# basic_levitator.net
KiCad netlist of a schematic drawn in EAGLE
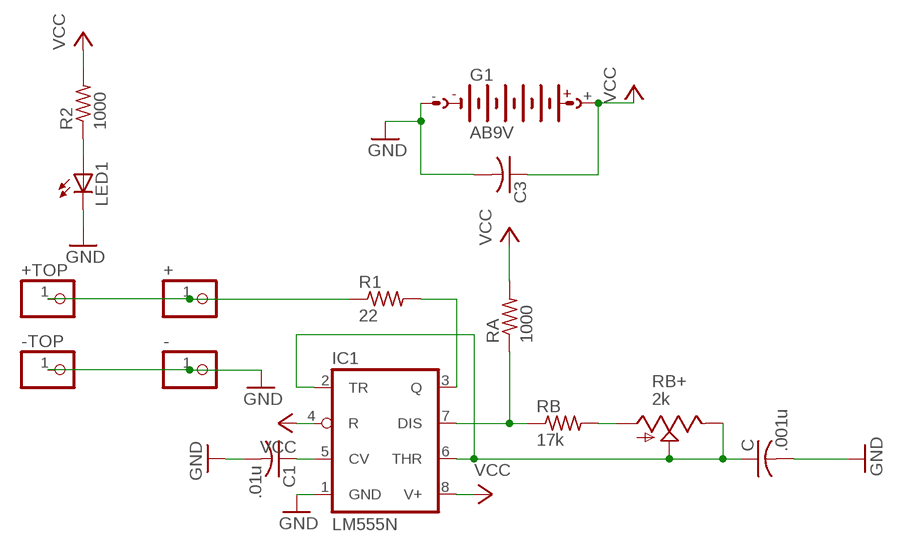
[diagram p0: schematic, sheet 1]

(export (version "E")
  (design (tool "Eeschema 10.0.6"))
  (components
    (comp (ref "+")
      (value "PINHD-1X1")
      (footprint "eagle-import:1X01")
      (libsource (lib "eagle-import") (part "PINHD-1X1"))
    )
    (comp (ref "+TOP")
      (value "PINHD-1X1")
      (footprint "eagle-import:1X01")
      (libsource (lib "eagle-import") (part "PINHD-1X1"))
    )
    (comp (ref "-")
      (value "PINHD-1X1")
      (footprint "eagle-import:1X01")
      (libsource (lib "eagle-import") (part "PINHD-1X1"))
    )
    (comp (ref "-TOP")
      (value "PINHD-1X1")
      (footprint "eagle-import:1X01")
      (libsource (lib "eagle-import") (part "PINHD-1X1"))
    )
    (comp (ref "C")
      (value ".001u")
      (footprint "eagle-import:C025-024X044")
      (libsource (lib "eagle-import") (part "C-US025-024X044"))
    )
    (comp (ref "C1")
      (value ".01u")
      (footprint "eagle-import:C025-025X050")
      (libsource (lib "eagle-import") (part "C-US025-025X050"))
    )
    (comp (ref "C3")
      (value "C-US050-024X044")
      (footprint "eagle-import:C050-024X044")
      (libsource (lib "eagle-import") (part "resistor_C-US050-024X044"))
    )
    (comp (ref "G1")
      (value "AB9V")
      (footprint "eagle-import:AB9V")
      (libsource (lib "eagle-import") (part "AB9V"))
    )
    (comp (ref "IC1")
      (value "LM555N")
      (footprint "eagle-import:DIL08")
      (libsource (lib "eagle-import") (part "555NLM"))
    )
    (comp (ref "LED1")
      (value "LED3MM")
      (footprint "eagle-import:LED3MM")
      (libsource (lib "eagle-import") (part "LED3MM"))
    )
    (comp (ref "R1")
      (value "22")
      (footprint "eagle-import:0207_10")
      (libsource (lib "eagle-import") (part "R-US_0207/10"))
    )
    (comp (ref "R2")
      (value "1000")
      (footprint "eagle-import:0207_10")
      (libsource (lib "eagle-import") (part "R-US_0207/10"))
    )
    (comp (ref "RA")
      (value "1000")
      (footprint "eagle-import:0207_10")
      (libsource (lib "eagle-import") (part "R-US_0207/10"))
    )
    (comp (ref "RB")
      (value "17k")
      (footprint "eagle-import:0207_10")
      (libsource (lib "eagle-import") (part "R-US_0207/10"))
    )
    (comp (ref "RB+")
      (value "2k")
      (footprint "eagle-import:CA6V")
      (libsource (lib "eagle-import") (part "TRIM_US-CA6V"))
    )
  )
  (nets
    (net (code "1") (name "GND") (class "Default")
      (node (ref "-") (pin "1") (pinfunction "1_1") (pintype "passive"))
      (node (ref "-TOP") (pin "1") (pinfunction "1_1") (pintype "passive"))
      (node (ref "C") (pin "2") (pinfunction "2_2") (pintype "passive"))
      (node (ref "C1") (pin "2") (pinfunction "2_2") (pintype "passive"))
      (node (ref "C3") (pin "2") (pinfunction "2_2") (pintype "passive"))
      (node (ref "G1") (pin "-") (pinfunction "-_-") (pintype "passive"))
      (node (ref "IC1") (pin "1") (pinfunction "GND_1") (pintype "power_in"))
      (node (ref "LED1") (pin "K") (pinfunction "C_K") (pintype "passive"))
    )
    (net (code "2") (name "Net-(+-Pad1)") (class "Default")
      (node (ref "+") (pin "1") (pinfunction "1_1") (pintype "passive"))
      (node (ref "+TOP") (pin "1") (pinfunction "1_1") (pintype "passive"))
      (node (ref "R1") (pin "1") (pinfunction "1_1") (pintype "passive"))
    )
    (net (code "3") (name "Net-(IC1-CV)") (class "Default")
      (node (ref "C1") (pin "1") (pinfunction "1_1") (pintype "passive"))
      (node (ref "IC1") (pin "5") (pinfunction "CV_5") (pintype "input"))
    )
    (net (code "4") (name "Net-(IC1-DIS)") (class "Default")
      (node (ref "IC1") (pin "7") (pinfunction "DIS_7") (pintype "input"))
      (node (ref "RA") (pin "1") (pinfunction "1_1") (pintype "passive"))
      (node (ref "RB") (pin "1") (pinfunction "1_1") (pintype "passive"))
    )
    (net (code "5") (name "Net-(IC1-Q)") (class "Default")
      (node (ref "IC1") (pin "3") (pinfunction "Q_3") (pintype "output"))
      (node (ref "R1") (pin "2") (pinfunction "2_2") (pintype "passive"))
    )
    (net (code "6") (name "Net-(IC1-THR)") (class "Default")
      (node (ref "C") (pin "1") (pinfunction "1_1") (pintype "passive"))
      (node (ref "IC1") (pin "2") (pinfunction "TR_2") (pintype "input"))
      (node (ref "IC1") (pin "6") (pinfunction "THR_6") (pintype "input"))
      (node (ref "RB+") (pin "E") (pinfunction "E_E") (pintype "passive"))
      (node (ref "RB+") (pin "S") (pinfunction "S_S") (pintype "passive"))
    )
    (net (code "7") (name "Net-(LED1-PadA)") (class "Default")
      (node (ref "LED1") (pin "A") (pinfunction "A_A") (pintype "passive"))
      (node (ref "R2") (pin "1") (pinfunction "1_1") (pintype "passive"))
    )
    (net (code "8") (name "Net-(RB+-PadA)") (class "Default")
      (node (ref "RB") (pin "2") (pinfunction "2_2") (pintype "passive"))
      (node (ref "RB+") (pin "A") (pinfunction "A_A") (pintype "passive"))
    )
    (net (code "9") (name "VCC") (class "Default")
      (node (ref "C3") (pin "1") (pinfunction "1_1") (pintype "passive"))
      (node (ref "G1") (pin "+") (pinfunction "+_+") (pintype "passive"))
      (node (ref "IC1") (pin "4") (pinfunction "R_4") (pintype "input"))
      (node (ref "IC1") (pin "8") (pinfunction "V+_8") (pintype "power_in"))
      (node (ref "R2") (pin "2") (pinfunction "2_2") (pintype "passive"))
      (node (ref "RA") (pin "2") (pinfunction "2_2") (pintype "passive"))
    )
  )
)
